# sprinkler_photon_0v1.net
KiCad netlist of a schematic drawn in Altium Designer
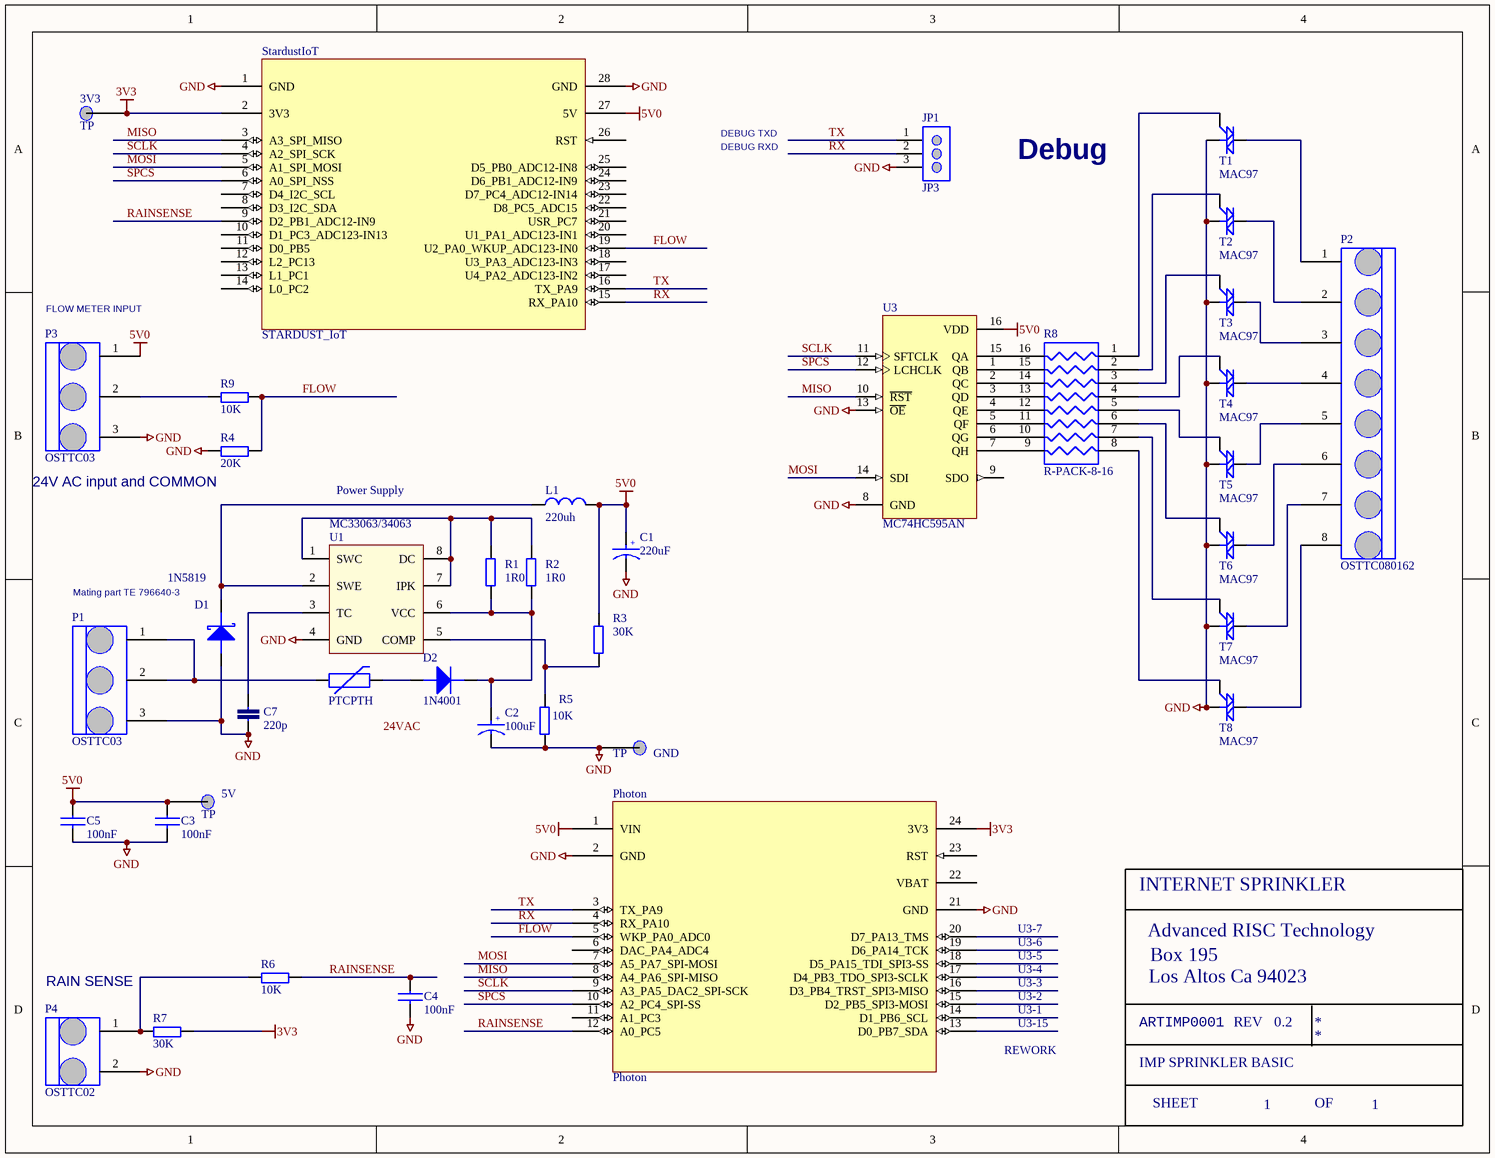
[diagram p0: sprinkler_photon_0v1.SchDoc]

(export (version "E")
  (design (tool "Eeschema 10.0.6"))
  (components
    (comp (ref "3V3")
      (value "TP")
      (footprint "SIP-1")
      (description "Test Point")
      (libsource (lib "visible_energy") (part "TPS"))
    )
    (comp (ref "5V")
      (value "TP")
      (footprint "SIP-1")
      (description "Test Point")
      (libsource (lib "visible_energy") (part "TPS"))
    )
    (comp (ref "C1")
      (value "220uF")
      (footprint "RB-2MM-5MM")
      (description "CAP ALUM 220UF 6.3V 20% RADIAL")
      (fields (field (name "DISTRIBUTOR PART#") "493-1004-ND") (field (name "MANUFACTURER") "Nichicon"))
      (libsource (lib "visible_energy") (part "CAP POL"))
    )
    (comp (ref "C2")
      (value "100uF")
      (footprint "RB-3.5MM-8MM")
      (description "CAP ALUM 100UF 50V 20% RADIAL")
      (fields (field (name "DISTRIBUTOR PART#") "493-1107-ND") (field (name "MANUFACTURER") "Nichicon"))
      (libsource (lib "visible_energy") (part "CAP POL"))
    )
    (comp (ref "C3")
      (value "100nF")
      (footprint "RAD-0.1")
      (description "CAP CER 0.1UF 25V 10% RADIAL")
      (fields (field (name "DISTRIBUTOR PART#") "445-8421-ND") (field (name "MANUFACTURER") "TDK"))
      (libsource (lib "visible_energy") (part "CAP NP"))
    )
    (comp (ref "C4")
      (value "100nF")
      (footprint "RAD-0.1")
      (description "CAP CER 0.1UF 25V 10% RADIAL")
      (fields (field (name "DISTRIBUTOR PART#") "445-8421-ND") (field (name "MANUFACTURER") "TDK"))
      (libsource (lib "visible_energy") (part "CAP NP"))
    )
    (comp (ref "C5")
      (value "100nF")
      (footprint "RAD-0.1")
      (description "CAP CER 0.1UF 25V 10% RADIAL")
      (fields (field (name "DISTRIBUTOR PART#") "445-8421-ND") (field (name "MANUFACTURER") "TDK"))
      (libsource (lib "visible_energy") (part "CAP NP"))
    )
    (comp (ref "C7")
      (value "220p")
      (footprint "thruholepcb:RADCAP-0.1")
      (description "CAP CER 220PF 100V 5% RADIAL")
      (fields (field (name "DISTRIBUTOR PART#") "478-4847-ND") (field (name "MANUFACTURER") "AVX"))
      (libsource (lib "rcl") (part "C-EU025-024X044"))
    )
    (comp (ref "D1")
      (value "1N5819")
      (footprint "AXIAL-0.4 - DIODE")
      (description "DIODE SCHOTTKY 40V 1A DO-41")
      (fields (field (name "MANUFACTURER") "Diodes") (field (name "MANUFACTURER PART#") "1N5819-T"))
      (libsource (lib "visible_energy") (part "DIODE SCHOTTKY"))
    )
    (comp (ref "D2")
      (value "1N4001")
      (footprint "AXIAL-0.4 - DIODE")
      (description "RECTIFIER 50V 1A DO-41")
      (fields (field (name "MANUFACTURER") "Diodes") (field (name "MANUFACTURER PART#") "1N4001-T"))
      (libsource (lib "visible_energy") (part "DIODE"))
    )
    (comp (ref "GND")
      (value "TP")
      (footprint "SIP-1")
      (description "Test Point")
      (libsource (lib "visible_energy") (part "TPS"))
    )
    (comp (ref "JP1")
      (value "JP3")
      (footprint "SIP-3")
      (description "3 PIN JUMPER")
      (libsource (lib "connector") (part "JP3"))
    )
    (comp (ref "L1")
      (value "220uh")
      (footprint "thruholepcb:RB-5MM - 9MMDIA")
      (description "Inductor")
      (fields (field (name "MANUFACTURER") "Abracon") (field (name "DISTRIBUTOR PART#") "AIUR-02H-221K-ND"))
      (libsource (lib "visible_energy") (part "INDUCTOR"))
    )
    (comp (ref "P1")
      (value "OSTTC03")
      (footprint "OSTTC03")
      (description "TERMINAL BLOCK 5MM VERT 3POS PCB")
      (fields (field (name "MANUFACTURER") "Onshore") (field (name "DISTRIBUTOR PART#") "ED2601-ND"))
      (libsource (lib "connector") (part "3PIN-POW"))
    )
    (comp (ref "P2")
      (value "OSTTC080162")
      (footprint "OSTTC08")
      (description "TERMINAL BLOCK 5MM VERT 8POS PCB")
      (fields (field (name "MANUFACTURER") "OnShore") (field (name "DISTRIBUTOR PART#") "ED2606-ND"))
      (libsource (lib "connector") (part "8PIN-POW"))
    )
    (comp (ref "P3")
      (value "OSTTC03")
      (footprint "OSTTC03")
      (description "TERMINAL BLOCK 5MM VERT 3POS PCB")
      (fields (field (name "MANUFACTURER") "Onshore") (field (name "DISTRIBUTOR PART#") "ED2601-ND"))
      (libsource (lib "connector") (part "3PIN-POW"))
    )
    (comp (ref "P4")
      (value "OSTTC02")
      (footprint "OSTTC02")
      (description "TERMINAL BLOCK 5MM VERT 2POS PCB")
      (fields (field (name "MANUFACTURER") "Onshore") (field (name "DISTRIBUTOR PART#") "ED2600-ND"))
      (libsource (lib "connector") (part "2PIN-POW"))
    )
    (comp (ref "Photon")
      (value "Photon")
      (footprint "PHOTON")
      (libsource (lib "visible_energy") (part "Photon"))
    )
    (comp (ref "PTC")
      (value "PTCPTH")
      (footprint "PTC")
      (description "FUSE PTC RESETTABLE .75A HOLD")
      (fields (field (name "DISTRIBUTOR PART#") "MF-R075-ND") (field (name "MANUFACTURER") "Bournes"))
      (libsource (lib "imp_sprinkler_0v1") (part "PTCPTH"))
    )
    (comp (ref "R1")
      (value "1R0")
      (footprint "AXIAL-0.4")
      (fields
        (field (name "DISTRIBUTOR PART#") "S1HCT-ND")
        (field (name "MANUFACTURER") "Stackpole")
        (field (name "MANUFACTURER PART#") "CFM12JT1R00")
      )
      (libsource (lib "rcl") (part "R-EU_0204/2V"))
    )
    (comp (ref "R2")
      (value "1R0")
      (footprint "AXIAL-0.4")
      (description "RES 1 OHM 1/2W 5% CF MINI")
      (fields (field (name "DISTRIBUTOR PART#") "S1HCT-ND") (field (name "MANUFACTURER") "Stackpole"))
      (libsource (lib "rcl") (part "R-EU_0204/2V"))
    )
    (comp (ref "R3")
      (value "30K")
      (footprint "AXIAL-0.4")
      (description "RES 30.1K OHM MET FILM .40W 1%")
      (fields (field (name "DISTRIBUTOR PART#") "PPC30.1KYCT-ND") (field (name "MANUFACTURER") "Vishay"))
      (libsource (lib "rcl") (part "R-EU_0204/7"))
    )
    (comp (ref "R4")
      (value "20K")
      (footprint "AXIAL-0.4")
      (description "RES 20K OHM 1/4W 5% CARBON FILM")
      (fields (field (name "DISTRIBUTOR PART#") "S10KQCT-ND") (field (name "MANUFACTURER") "Stackpole"))
      (libsource (lib "rcl") (part "R-EU_0204/7"))
    )
    (comp (ref "R5")
      (value "10K")
      (footprint "AXIAL-0.4")
      (description "RES MF 1/4W 10K OHM 1% AXIAL")
      (fields
        (field (name "DISTRIBUTOR PART#") "RNF14FTD10K0CT-ND")
        (field (name "MANUFACTURER") "Stackpole")
      )
      (libsource (lib "rcl") (part "R-EU_0204/7"))
    )
    (comp (ref "R6")
      (value "10K")
      (footprint "AXIAL-0.4")
      (description "RES 10K OHM 1/4W 5% CF MINI")
      (fields (field (name "DISTRIBUTOR PART#") "S10KQCT-ND") (field (name "MANUFACTURER") "Stackpole"))
      (libsource (lib "rcl") (part "R-EU_0204/7"))
    )
    (comp (ref "R7")
      (value "30K")
      (footprint "AXIAL-0.4")
      (description "RES 30.1K OHM MET FILM .40W 1%")
      (fields (field (name "DISTRIBUTOR PART#") "PPC30.1KYCT-ND") (field (name "MANUFACTURER") "Vishay"))
      (libsource (lib "rcl") (part "R-EU_0204/7"))
    )
    (comp (ref "R8")
      (value "R-PACK-8-16")
      (footprint "DIP-16")
      (description "RES ARRAY 330 OHM 8 RES 16-DIP")
      (fields (field (name "MANUFACTURER") "Bournes") (field (name "DISTRIBUTOR PART#") "4116R-1-331LF-ND"))
      (libsource (lib "descrete") (part "R-PACK-8-16"))
    )
    (comp (ref "R9")
      (value "10K")
      (footprint "AXIAL-0.4")
      (description "RES 10K OHM 1/4W 5% CF MINI")
      (fields (field (name "DISTRIBUTOR PART#") "S10KQCT-ND") (field (name "MANUFACTURER") "Stackpole"))
      (libsource (lib "rcl") (part "R-EU_0204/7"))
    )
    (comp (ref "StardustIoT")
      (value "STARDUST_IoT")
      (footprint "Stardust_IoT")
      (libsource (lib "visible_energy") (part "Stardust_IoT"))
    )
    (comp (ref "T1")
      (value "MAC97")
      (footprint "imp_sprinkler_0v1:TO-92")
      (description "THYRISTOR TRIAC .6A 600V TO92")
      (fields (field (name "DISTRIBUTOR PART#") "MAC97A8GOS-ND") (field (name "MANUFACTURER") "ON"))
      (libsource (lib "SparkFun") (part "LX807DE"))
    )
    (comp (ref "T2")
      (value "MAC97")
      (footprint "imp_sprinkler_0v1:TO-92")
      (description "THYRISTOR TRIAC .6A 600V TO92")
      (fields (field (name "DISTRIBUTOR PART#") "MAC97A8GOS-ND") (field (name "MANUFACTURER") "ON"))
      (libsource (lib "SparkFun") (part "LX807DE"))
    )
    (comp (ref "T3")
      (value "MAC97")
      (footprint "TO-92")
      (description "THYRISTOR TRIAC .6A 600V TO92")
      (fields (field (name "DISTRIBUTOR PART#") "MAC97A8GOS-ND") (field (name "MANUFACTURER") "ON"))
      (libsource (lib "SparkFun") (part "LX807DE"))
    )
    (comp (ref "T4")
      (value "MAC97")
      (footprint "TO-92")
      (description "THYRISTOR TRIAC .6A 600V TO92")
      (fields (field (name "DISTRIBUTOR PART#") "MAC97A8GOS-ND") (field (name "MANUFACTURER") "ON"))
      (libsource (lib "SparkFun") (part "LX807DE"))
    )
    (comp (ref "T5")
      (value "MAC97")
      (footprint "TO-92")
      (description "THYRISTOR TRIAC .6A 600V TO92")
      (fields (field (name "DISTRIBUTOR PART#") "MAC97A8GOS-ND") (field (name "MANUFACTURER") "ON"))
      (libsource (lib "SparkFun") (part "LX807DE"))
    )
    (comp (ref "T6")
      (value "MAC97")
      (footprint "TO-92")
      (description "THYRISTOR TRIAC .6A 600V TO92")
      (fields (field (name "DISTRIBUTOR PART#") "MAC97A8GOS-ND") (field (name "MANUFACTURER") "ON"))
      (libsource (lib "SparkFun") (part "LX807DE"))
    )
    (comp (ref "T7")
      (value "MAC97")
      (footprint "TO-92")
      (description "THYRISTOR TRIAC .6A 600V TO92")
      (fields (field (name "DISTRIBUTOR PART#") "MAC97A8GOS-ND") (field (name "MANUFACTURER") "ON"))
      (libsource (lib "SparkFun") (part "LX807DE"))
    )
    (comp (ref "T8")
      (value "MAC97")
      (footprint "TO-92")
      (description "THYRISTOR TRIAC .6A 600V TO92")
      (fields (field (name "DISTRIBUTOR PART#") "MAC97A8GOS-ND") (field (name "MANUFACTURER") "ON"))
      (libsource (lib "SparkFun") (part "LX807DE"))
    )
    (comp (ref "U1")
      (value "MC33063/34063")
      (footprint "DIP8")
      (fields
        (field (name "DISTRIBUTOR PART#") "296-17764-5-ND")
        (field (name "MANUFACTURER") "TI")
        (field (name "MANUFACTURER PART#") "MC33063AP")
      )
      (libsource (lib "IC") (part "MC33063/MC34063P"))
    )
    (comp (ref "U3")
      (value "MC74HC595AN")
      (footprint "DIP-16")
      (description "8-Bit Serial-Input/Serial or Prallel-Output Shift Register with Latched 3-State Outputs")
      (fields
        (field (name "DISTRIBUTOR PART#") "MC74HC595ANGOS-ND")
        (field (name "MANUFACTURER") "ON Semiconductor")
      )
      (libsource (lib "ON Semi Logic Register") (part "MC74HC595AN"))
    )
  )
  (nets
    (net (code "2") (name "/FLOW") (class "Default")
      (node (ref "Photon") (pin "5") (pinfunction "WKP_PA0_ADC0_5") (pintype "bidirectional"))
      (node (ref "R4") (pin "2") (pinfunction "2_2") (pintype "passive"))
      (node (ref "R9") (pin "2") (pinfunction "2_2") (pintype "passive"))
      (node (ref "StardustIoT") (pin "19") (pinfunction "U2_PA0_WKUP_ADC123-IN0_19") (pintype "bidirectional"))
    )
    (net (code "3") (name "/MISO") (class "Default")
      (node (ref "Photon") (pin "8") (pinfunction "A4_PA6_SPI-MISO_8") (pintype "bidirectional"))
      (node (ref "StardustIoT") (pin "3") (pinfunction "A3_SPI_MISO_3") (pintype "bidirectional"))
      (node (ref "U3") (pin "10") (pinfunction "~{RST}_10") (pintype "input"))
    )
    (net (code "4") (name "/MOSI") (class "Default")
      (node (ref "Photon") (pin "7") (pinfunction "A5_PA7_SPI-MOSI_7") (pintype "bidirectional"))
      (node (ref "StardustIoT") (pin "5") (pinfunction "A1_SPI_MOSI_5") (pintype "bidirectional"))
      (node (ref "U3") (pin "14") (pinfunction "SDI_14") (pintype "input"))
    )
    (net (code "5") (name "/RAINSENSE") (class "Default")
      (node (ref "C4") (pin "1") (pinfunction "1_1") (pintype "passive"))
      (node (ref "Photon") (pin "12") (pinfunction "A0_PC5_12") (pintype "bidirectional"))
      (node (ref "R6") (pin "2") (pinfunction "2_2") (pintype "passive"))
      (node (ref "StardustIoT") (pin "9") (pinfunction "D2_PB1_ADC12-IN9_9") (pintype "bidirectional"))
    )
    (net (code "6") (name "/RX") (class "Default")
      (node (ref "JP1") (pin "2") (pinfunction "2_2") (pintype "passive"))
      (node (ref "Photon") (pin "4") (pinfunction "RX_PA10_4") (pintype "bidirectional"))
      (node (ref "StardustIoT") (pin "15") (pinfunction "RX_PA10_15") (pintype "bidirectional"))
    )
    (net (code "7") (name "/SCLK") (class "Default")
      (node (ref "Photon") (pin "9") (pinfunction "A3_PA5_DAC2_SPI-SCK_9") (pintype "bidirectional"))
      (node (ref "StardustIoT") (pin "4") (pinfunction "A2_SPI_SCK_4") (pintype "bidirectional"))
      (node (ref "U3") (pin "11") (pinfunction "SFTCLK_11") (pintype "input"))
    )
    (net (code "8") (name "/SPCS") (class "Default")
      (node (ref "Photon") (pin "10") (pinfunction "A2_PC4_SPI-SS_10") (pintype "bidirectional"))
      (node (ref "StardustIoT") (pin "6") (pinfunction "A0_SPI_NSS_6") (pintype "bidirectional"))
      (node (ref "U3") (pin "12") (pinfunction "LCHCLK_12") (pintype "input"))
    )
    (net (code "9") (name "/TX") (class "Default")
      (node (ref "JP1") (pin "1") (pinfunction "1_1") (pintype "passive"))
      (node (ref "Photon") (pin "3") (pinfunction "TX_PA9_3") (pintype "bidirectional"))
      (node (ref "StardustIoT") (pin "16") (pinfunction "TX_PA9_16") (pintype "bidirectional"))
    )
    (net (code "10") (name "3V3") (class "Default")
      (node (ref "3V3") (pin "1") (pinfunction "1_1") (pintype "passive"))
      (node (ref "Photon") (pin "24") (pinfunction "3V3_24") (pintype "power_in"))
      (node (ref "R7") (pin "2") (pinfunction "2_2") (pintype "passive"))
      (node (ref "StardustIoT") (pin "2") (pinfunction "3V3_2") (pintype "power_in"))
    )
    (net (code "11") (name "5V0") (class "Default")
      (node (ref "5V") (pin "1") (pinfunction "1_1") (pintype "passive"))
      (node (ref "C1") (pin "1") (pinfunction "1_1") (pintype "passive"))
      (node (ref "C3") (pin "1") (pinfunction "1_1") (pintype "passive"))
      (node (ref "C5") (pin "1") (pinfunction "1_1") (pintype "passive"))
      (node (ref "L1") (pin "2") (pinfunction "2_2") (pintype "passive"))
      (node (ref "P3") (pin "1") (pintype "passive"))
      (node (ref "Photon") (pin "1") (pinfunction "VIN_1") (pintype "power_in"))
      (node (ref "R3") (pin "1") (pinfunction "1_1") (pintype "passive"))
      (node (ref "StardustIoT") (pin "27") (pinfunction "5V_27") (pintype "power_in"))
      (node (ref "U3") (pin "16") (pinfunction "VDD_16") (pintype "power_in"))
    )
    (net (code "12") (name "GND") (class "Default")
      (node (ref "C1") (pin "2") (pinfunction "2_2") (pintype "passive"))
      (node (ref "C2") (pin "2") (pinfunction "2_2") (pintype "passive"))
      (node (ref "C3") (pin "2") (pinfunction "2_2") (pintype "passive"))
      (node (ref "C4") (pin "2") (pinfunction "2_2") (pintype "passive"))
      (node (ref "C5") (pin "2") (pinfunction "2_2") (pintype "passive"))
      (node (ref "C7") (pin "2") (pinfunction "2_2") (pintype "passive"))
      (node (ref "D1") (pin "1") (pinfunction "A_1") (pintype "passive"))
      (node (ref "GND") (pin "1") (pinfunction "1_1") (pintype "passive"))
      (node (ref "JP1") (pin "3") (pinfunction "3_3") (pintype "passive"))
      (node (ref "P1") (pin "3") (pintype "passive"))
      (node (ref "P3") (pin "3") (pintype "passive"))
      (node (ref "P4") (pin "2") (pintype "passive"))
      (node (ref "Photon") (pin "2") (pinfunction "GND_2") (pintype "power_in"))
      (node (ref "Photon") (pin "21") (pinfunction "GND_21") (pintype "power_in"))
      (node (ref "R4") (pin "1") (pinfunction "1_1") (pintype "passive"))
      (node (ref "R5") (pin "2") (pinfunction "2_2") (pintype "passive"))
      (node (ref "StardustIoT") (pin "1") (pinfunction "GND_1") (pintype "power_in"))
      (node (ref "StardustIoT") (pin "28") (pinfunction "GND_28") (pintype "power_in"))
      (node (ref "T1") (pin "1") (pinfunction "M1_1") (pintype "passive"))
      (node (ref "T2") (pin "1") (pinfunction "M1_1") (pintype "passive"))
      (node (ref "T3") (pin "1") (pinfunction "M1_1") (pintype "passive"))
      (node (ref "T4") (pin "1") (pinfunction "M1_1") (pintype "passive"))
      (node (ref "T5") (pin "1") (pinfunction "M1_1") (pintype "passive"))
      (node (ref "T6") (pin "1") (pinfunction "M1_1") (pintype "passive"))
      (node (ref "T7") (pin "1") (pinfunction "M1_1") (pintype "passive"))
      (node (ref "T8") (pin "1") (pinfunction "M1_1") (pintype "passive"))
      (node (ref "U1") (pin "4") (pinfunction "GND_4") (pintype "passive"))
      (node (ref "U3") (pin "13") (pinfunction "~{OE}_13") (pintype "input"))
      (node (ref "U3") (pin "8") (pinfunction "GND_8") (pintype "power_in"))
    )
    (net (code "13") (name "Net-(D1-K)") (class "Default")
      (node (ref "D1") (pin "2") (pinfunction "K_2") (pintype "passive"))
      (node (ref "L1") (pin "1") (pinfunction "1_1") (pintype "passive"))
      (node (ref "U1") (pin "2") (pinfunction "SWE_2") (pintype "passive"))
    )
    (net (code "14") (name "Net-(D2-A)") (class "Default")
      (node (ref "D2") (pin "1") (pinfunction "A_1") (pintype "passive"))
      (node (ref "PTC") (pin "2") (pinfunction "2_2") (pintype "passive"))
    )
    (net (code "15") (name "Net-(D2-K)") (class "Default")
      (node (ref "C2") (pin "1") (pinfunction "1_1") (pintype "passive"))
      (node (ref "D2") (pin "2") (pinfunction "K_2") (pintype "passive"))
      (node (ref "R1") (pin "2") (pinfunction "2_2") (pintype "passive"))
      (node (ref "R2") (pin "2") (pinfunction "2_2") (pintype "passive"))
      (node (ref "U1") (pin "6") (pinfunction "VCC_6") (pintype "passive"))
    )
    (net (code "16") (name "Net-(P1-Pad1)") (class "Default")
      (node (ref "P1") (pin "1") (pintype "passive"))
      (node (ref "P1") (pin "2") (pintype "passive"))
      (node (ref "PTC") (pin "1") (pinfunction "1_1") (pintype "passive"))
    )
    (net (code "17") (name "Net-(P3-Pad2)") (class "Default")
      (node (ref "P3") (pin "2") (pintype "passive"))
      (node (ref "R9") (pin "1") (pinfunction "1_1") (pintype "passive"))
    )
    (net (code "18") (name "Net-(P4-Pad1)") (class "Default")
      (node (ref "P4") (pin "1") (pintype "passive"))
      (node (ref "R6") (pin "1") (pinfunction "1_1") (pintype "passive"))
      (node (ref "R7") (pin "1") (pinfunction "1_1") (pintype "passive"))
    )
    (net (code "19") (name "Net-(T1-G)") (class "Default")
      (node (ref "R8") (pin "1") (pinfunction "R1_1") (pintype "passive"))
      (node (ref "T1") (pin "2") (pinfunction "G_2") (pintype "passive"))
    )
    (net (code "20") (name "Net-(T1-M2)") (class "Default")
      (node (ref "P2") (pin "1") (pintype "passive"))
      (node (ref "T1") (pin "3") (pinfunction "M2_3") (pintype "passive"))
    )
    (net (code "21") (name "Net-(T2-G)") (class "Default")
      (node (ref "R8") (pin "2") (pinfunction "R2_2") (pintype "passive"))
      (node (ref "T2") (pin "2") (pinfunction "G_2") (pintype "passive"))
    )
    (net (code "22") (name "Net-(T2-M2)") (class "Default")
      (node (ref "P2") (pin "2") (pintype "passive"))
      (node (ref "T2") (pin "3") (pinfunction "M2_3") (pintype "passive"))
    )
    (net (code "23") (name "Net-(T3-G)") (class "Default")
      (node (ref "R8") (pin "3") (pinfunction "R3_3") (pintype "passive"))
      (node (ref "T3") (pin "2") (pinfunction "G_2") (pintype "passive"))
    )
    (net (code "24") (name "Net-(T3-M2)") (class "Default")
      (node (ref "P2") (pin "3") (pintype "passive"))
      (node (ref "T3") (pin "3") (pinfunction "M2_3") (pintype "passive"))
    )
    (net (code "25") (name "Net-(T4-G)") (class "Default")
      (node (ref "R8") (pin "4") (pinfunction "R4_4") (pintype "passive"))
      (node (ref "T4") (pin "2") (pinfunction "G_2") (pintype "passive"))
    )
    (net (code "26") (name "Net-(T4-M2)") (class "Default")
      (node (ref "P2") (pin "4") (pintype "passive"))
      (node (ref "T4") (pin "3") (pinfunction "M2_3") (pintype "passive"))
    )
    (net (code "27") (name "Net-(T5-G)") (class "Default")
      (node (ref "R8") (pin "5") (pinfunction "R5_5") (pintype "passive"))
      (node (ref "T5") (pin "2") (pinfunction "G_2") (pintype "passive"))
    )
    (net (code "28") (name "Net-(T5-M2)") (class "Default")
      (node (ref "P2") (pin "5") (pintype "passive"))
      (node (ref "T5") (pin "3") (pinfunction "M2_3") (pintype "passive"))
    )
    (net (code "29") (name "Net-(T6-G)") (class "Default")
      (node (ref "R8") (pin "6") (pinfunction "R6_6") (pintype "passive"))
      (node (ref "T6") (pin "2") (pinfunction "G_2") (pintype "passive"))
    )
    (net (code "30") (name "Net-(T6-M2)") (class "Default")
      (node (ref "P2") (pin "6") (pintype "passive"))
      (node (ref "T6") (pin "3") (pinfunction "M2_3") (pintype "passive"))
    )
    (net (code "31") (name "Net-(T7-G)") (class "Default")
      (node (ref "R8") (pin "7") (pinfunction "R7_7") (pintype "passive"))
      (node (ref "T7") (pin "2") (pinfunction "G_2") (pintype "passive"))
    )
    (net (code "32") (name "Net-(T7-M2)") (class "Default")
      (node (ref "P2") (pin "7") (pintype "passive"))
      (node (ref "T7") (pin "3") (pinfunction "M2_3") (pintype "passive"))
    )
    (net (code "33") (name "Net-(T8-G)") (class "Default")
      (node (ref "R8") (pin "8") (pinfunction "R8_8") (pintype "passive"))
      (node (ref "T8") (pin "2") (pinfunction "G_2") (pintype "passive"))
    )
    (net (code "34") (name "Net-(T8-M2)") (class "Default")
      (node (ref "P2") (pin "8") (pintype "passive"))
      (node (ref "T8") (pin "3") (pinfunction "M2_3") (pintype "passive"))
    )
    (net (code "35") (name "Net-(U1-COMP)") (class "Default")
      (node (ref "R3") (pin "2") (pinfunction "2_2") (pintype "passive"))
      (node (ref "R5") (pin "1") (pinfunction "1_1") (pintype "passive"))
      (node (ref "U1") (pin "5") (pinfunction "COMP_5") (pintype "passive"))
    )
    (net (code "36") (name "Net-(U1-DC)") (class "Default")
      (node (ref "R1") (pin "1") (pinfunction "1_1") (pintype "passive"))
      (node (ref "R2") (pin "1") (pinfunction "1_1") (pintype "passive"))
      (node (ref "U1") (pin "1") (pinfunction "SWC_1") (pintype "passive"))
      (node (ref "U1") (pin "7") (pinfunction "IPK_7") (pintype "passive"))
      (node (ref "U1") (pin "8") (pinfunction "DC_8") (pintype "passive"))
    )
    (net (code "37") (name "Net-(U1-TC)") (class "Default")
      (node (ref "C7") (pin "1") (pinfunction "1_1") (pintype "passive"))
      (node (ref "U1") (pin "3") (pinfunction "TC_3") (pintype "passive"))
    )
    (net (code "38") (name "Net-(U3-QA)") (class "Default")
      (node (ref "R8") (pin "16") (pinfunction "R1_16") (pintype "passive"))
      (node (ref "U3") (pin "15") (pinfunction "QA_15") (pintype "tri_state"))
    )
    (net (code "39") (name "Net-(U3-QB)") (class "Default")
      (node (ref "R8") (pin "15") (pinfunction "R2_15") (pintype "passive"))
      (node (ref "U3") (pin "1") (pinfunction "QB_1") (pintype "tri_state"))
    )
    (net (code "40") (name "Net-(U3-QC)") (class "Default")
      (node (ref "R8") (pin "14") (pinfunction "R3_14") (pintype "passive"))
      (node (ref "U3") (pin "2") (pinfunction "QC_2") (pintype "tri_state"))
    )
    (net (code "41") (name "Net-(U3-QD)") (class "Default")
      (node (ref "R8") (pin "13") (pinfunction "R4_13") (pintype "passive"))
      (node (ref "U3") (pin "3") (pinfunction "QD_3") (pintype "tri_state"))
    )
    (net (code "42") (name "Net-(U3-QE)") (class "Default")
      (node (ref "R8") (pin "12") (pinfunction "R5_12") (pintype "passive"))
      (node (ref "U3") (pin "4") (pinfunction "QE_4") (pintype "tri_state"))
    )
    (net (code "43") (name "Net-(U3-QF)") (class "Default")
      (node (ref "R8") (pin "11") (pinfunction "R6_11") (pintype "passive"))
      (node (ref "U3") (pin "5") (pinfunction "QF_5") (pintype "tri_state"))
    )
    (net (code "44") (name "Net-(U3-QG)") (class "Default")
      (node (ref "R8") (pin "10") (pinfunction "R7_10") (pintype "passive"))
      (node (ref "U3") (pin "6") (pinfunction "QG_6") (pintype "tri_state"))
    )
    (net (code "45") (name "Net-(U3-QH)") (class "Default")
      (node (ref "R8") (pin "9") (pinfunction "R8_9") (pintype "passive"))
      (node (ref "U3") (pin "7") (pinfunction "QH_7") (pintype "tri_state"))
    )
    (net (code "46") (name "unconnected-(Photon-A1_PC3-Pad11)") (class "Default")
      (node (ref "Photon") (pin "11") (pinfunction "A1_PC3_11") (pintype "bidirectional"))
    )
    (net (code "47") (name "unconnected-(Photon-D0_PB7_SDA-Pad13)") (class "Default")
      (node (ref "Photon") (pin "13") (pinfunction "D0_PB7_SDA_13") (pintype "bidirectional"))
    )
    (net (code "48") (name "unconnected-(Photon-D1_PB6_SCL-Pad14)") (class "Default")
      (node (ref "Photon") (pin "14") (pinfunction "D1_PB6_SCL_14") (pintype "bidirectional"))
    )
    (net (code "49") (name "unconnected-(Photon-D2_PB5_SPI3-MOSI-Pad15)") (class "Default")
      (node (ref "Photon") (pin "15") (pinfunction "D2_PB5_SPI3-MOSI_15") (pintype "bidirectional"))
    )
    (net (code "50") (name "unconnected-(Photon-D3_PB4_TRST_SPI3-MISO-Pad16)") (class "Default")
      (node (ref "Photon") (pin "16") (pinfunction "D3_PB4_TRST_SPI3-MISO_16") (pintype "bidirectional"))
    )
    (net (code "51") (name "unconnected-(Photon-D4_PB3_TDO_SPI3-SCLK-Pad17)") (class "Default")
      (node (ref "Photon") (pin "17") (pinfunction "D4_PB3_TDO_SPI3-SCLK_17") (pintype "bidirectional"))
    )
    (net (code "52") (name "unconnected-(Photon-D5_PA15_TDI_SPI3-SS-Pad18)") (class "Default")
      (node (ref "Photon") (pin "18") (pinfunction "D5_PA15_TDI_SPI3-SS_18") (pintype "bidirectional"))
    )
    (net (code "53") (name "unconnected-(Photon-D6_PA14_TCK-Pad19)") (class "Default")
      (node (ref "Photon") (pin "19") (pinfunction "D6_PA14_TCK_19") (pintype "bidirectional"))
    )
    (net (code "54") (name "unconnected-(Photon-D7_PA13_TMS-Pad20)") (class "Default")
      (node (ref "Photon") (pin "20") (pinfunction "D7_PA13_TMS_20") (pintype "bidirectional"))
    )
    (net (code "55") (name "unconnected-(Photon-DAC_PA4_ADC4-Pad6)") (class "Default")
      (node (ref "Photon") (pin "6") (pinfunction "DAC_PA4_ADC4_6") (pintype "bidirectional"))
    )
    (net (code "56") (name "unconnected-(Photon-RST-Pad23)") (class "Default")
      (node (ref "Photon") (pin "23") (pinfunction "RST_23") (pintype "input"))
    )
    (net (code "57") (name "unconnected-(Photon-VBAT-Pad22)") (class "Default")
      (node (ref "Photon") (pin "22") (pinfunction "VBAT_22") (pintype "power_in"))
    )
    (net (code "58") (name "unconnected-(StardustIoT-D0_PB5-Pad11)") (class "Default")
      (node (ref "StardustIoT") (pin "11") (pinfunction "D0_PB5_11") (pintype "bidirectional"))
    )
    (net (code "59") (name "unconnected-(StardustIoT-D1_PC3_ADC123-IN13-Pad10)") (class "Default")
      (node (ref "StardustIoT") (pin "10") (pinfunction "D1_PC3_ADC123-IN13_10") (pintype "bidirectional"))
    )
    (net (code "60") (name "unconnected-(StardustIoT-D3_I2C_SDA-Pad8)") (class "Default")
      (node (ref "StardustIoT") (pin "8") (pinfunction "D3_I2C_SDA_8") (pintype "bidirectional"))
    )
    (net (code "61") (name "unconnected-(StardustIoT-D4_I2C_SCL-Pad7)") (class "Default")
      (node (ref "StardustIoT") (pin "7") (pinfunction "D4_I2C_SCL_7") (pintype "bidirectional"))
    )
    (net (code "62") (name "unconnected-(StardustIoT-D5_PB0_ADC12-IN8-Pad25)") (class "Default")
      (node (ref "StardustIoT") (pin "25") (pinfunction "D5_PB0_ADC12-IN8_25") (pintype "bidirectional"))
    )
    (net (code "63") (name "unconnected-(StardustIoT-D6_PB1_ADC12-IN9-Pad24)") (class "Default")
      (node (ref "StardustIoT") (pin "24") (pinfunction "D6_PB1_ADC12-IN9_24") (pintype "bidirectional"))
    )
    (net (code "64") (name "unconnected-(StardustIoT-D7_PC4_ADC12-IN14-Pad23)") (class "Default")
      (node (ref "StardustIoT") (pin "23") (pinfunction "D7_PC4_ADC12-IN14_23") (pintype "bidirectional"))
    )
    (net (code "65") (name "unconnected-(StardustIoT-D8_PC5_ADC15-Pad22)") (class "Default")
      (node (ref "StardustIoT") (pin "22") (pinfunction "D8_PC5_ADC15_22") (pintype "bidirectional"))
    )
    (net (code "66") (name "unconnected-(StardustIoT-L0_PC2-Pad14)") (class "Default")
      (node (ref "StardustIoT") (pin "14") (pinfunction "L0_PC2_14") (pintype "bidirectional"))
    )
    (net (code "67") (name "unconnected-(StardustIoT-L1_PC1-Pad13)") (class "Default")
      (node (ref "StardustIoT") (pin "13") (pinfunction "L1_PC1_13") (pintype "bidirectional"))
    )
    (net (code "68") (name "unconnected-(StardustIoT-L2_PC13-Pad12)") (class "Default")
      (node (ref "StardustIoT") (pin "12") (pinfunction "L2_PC13_12") (pintype "bidirectional"))
    )
    (net (code "69") (name "unconnected-(StardustIoT-RST-Pad26)") (class "Default")
      (node (ref "StardustIoT") (pin "26") (pinfunction "RST_26") (pintype "input"))
    )
    (net (code "70") (name "unconnected-(StardustIoT-U1_PA1_ADC123-IN1-Pad20)") (class "Default")
      (node (ref "StardustIoT") (pin "20") (pinfunction "U1_PA1_ADC123-IN1_20") (pintype "bidirectional"))
    )
    (net (code "71") (name "unconnected-(StardustIoT-U3_PA3_ADC123-IN3-Pad18)") (class "Default")
      (node (ref "StardustIoT") (pin "18") (pinfunction "U3_PA3_ADC123-IN3_18") (pintype "bidirectional"))
    )
    (net (code "72") (name "unconnected-(StardustIoT-U4_PA2_ADC123-IN2-Pad17)") (class "Default")
      (node (ref "StardustIoT") (pin "17") (pinfunction "U4_PA2_ADC123-IN2_17") (pintype "bidirectional"))
    )
    (net (code "73") (name "unconnected-(StardustIoT-USR_PC7-Pad21)") (class "Default")
      (node (ref "StardustIoT") (pin "21") (pinfunction "USR_PC7_21") (pintype "bidirectional"))
    )
    (net (code "74") (name "unconnected-(U3-SDO-Pad9)") (class "Default")
      (node (ref "U3") (pin "9") (pinfunction "SDO_9") (pintype "output"))
    )
  )
)
